# Battery_Monitoring.net
KiCad netlist of a schematic drawn in Altium Designer
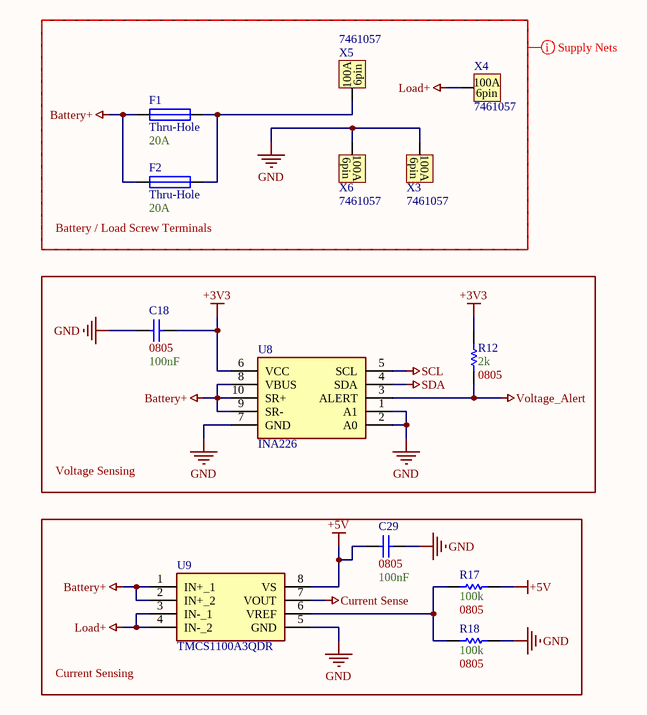
[diagram p0: Battery Monitoring.SchDoc]

(export (version "E")
  (design (tool "Eeschema 10.0.6"))
  (components
    (comp (ref "C18")
      (value "[Cap] SMD Nonpolarized")
      (footprint "[Cap] SMD 0805")
      (fields (field (name "SIZE PACKAGE") "0805") (field (name "CAPACITANCE") "100nF"))
      (libsource (lib "RADM Components") (part "[Cap] SMD Nonpolarized"))
    )
    (comp (ref "C29")
      (value "[Cap] SMD Nonpolarized")
      (footprint "[Cap] SMD 0805")
      (fields (field (name "SIZE PACKAGE") "0805") (field (name "CAPACITANCE") "100nF"))
      (libsource (lib "RADM Components") (part "[Cap] SMD Nonpolarized"))
    )
    (comp (ref "F1")
      (value "Thru-Hole")
      (footprint "[Fuse] Blade (2)")
      (fields (field (name "CAPACITY") "20A"))
      (libsource (lib "RADM Components") (part "[Fuse] Thru-Hole Blade"))
    )
    (comp (ref "F2")
      (value "Thru-Hole")
      (footprint "[Fuse] Blade (2)")
      (fields (field (name "CAPACITY") "20A"))
      (libsource (lib "RADM Components") (part "[Fuse] Thru-Hole Blade"))
    )
    (comp (ref "R12")
      (value "[Res] SMD Resistor")
      (footprint "[Res] SMD 0805")
      (fields (field (name "RESISTANCE") "2k") (field (name "SIZE PACKAGE") "0805"))
      (libsource (lib "RADM Components") (part "[Res] SMD Resistor"))
    )
    (comp (ref "R17")
      (value "[Res] SMD Resistor")
      (footprint "[Res] SMD 0805")
      (fields (field (name "RESISTANCE") "100k") (field (name "SIZE PACKAGE") "0805"))
      (libsource (lib "RADM Components") (part "[Res] SMD Resistor"))
    )
    (comp (ref "R18")
      (value "[Res] SMD Resistor")
      (footprint "[Res] SMD 0805")
      (fields (field (name "RESISTANCE") "100k") (field (name "SIZE PACKAGE") "0805"))
      (libsource (lib "RADM Components") (part "[Res] SMD Resistor"))
    )
    (comp (ref "U8")
      (value "INA226")
      (footprint "[IC] Battery Voltage Monitor (36V)")
      (description "INA226AIDGST")
      (libsource (lib "RADM Components") (part "[IC] Battery Voltage Monitor (36V)"))
    )
    (comp (ref "U9")
      (value "TMCS1100A3QDR")
      (footprint "[IC] Hall Effect Current Sensor")
      (description "TMCS1100")
      (libsource (lib "RADM Components") (part "[IC] Hall Effect Current Sensor"))
    )
    (comp (ref "X3")
      (value "7461057")
      (footprint "[Port] Shank Connector (100A)")
      (description "7461057, internal thread")
      (libsource (lib "") (part "[Port] Shank Connector (100A)_1"))
    )
    (comp (ref "X4")
      (value "7461057")
      (footprint "[Port] Shank Connector (100A)")
      (description "7461057, internal thread")
      (libsource (lib "") (part "[Port] Shank Connector (100A)_2"))
    )
    (comp (ref "X5")
      (value "7461057")
      (footprint "[Port] Shank Connector (100A)")
      (description "7461057, internal thread")
      (libsource (lib "RADM Components") (part "[Port] Shank Connector (100A)"))
    )
    (comp (ref "X6")
      (value "7461057")
      (footprint "[Port] Shank Connector (100A)")
      (description "7461057, internal thread")
      (libsource (lib "") (part "[Port] Shank Connector (100A)_1"))
    )
  )
  (nets
    (net (code "1") (name "+3V3") (class "Default")
      (node (ref "C18") (pin "1") (pinfunction "1_1") (pintype "passive"))
      (node (ref "R12") (pin "2") (pinfunction "2_2") (pintype "passive"))
      (node (ref "U8") (pin "6") (pinfunction "VCC_6") (pintype "passive"))
    )
    (net (code "2") (name "+5V") (class "Default")
      (node (ref "C29") (pin "2") (pinfunction "2_2") (pintype "passive"))
      (node (ref "R17") (pin "2") (pinfunction "2_2") (pintype "passive"))
      (node (ref "U9") (pin "8") (pinfunction "VS_8") (pintype "passive"))
    )
    (net (code "3") (name "Battery+") (class "Default")
      (node (ref "F1") (pin "1") (pinfunction "1_1") (pintype "passive"))
      (node (ref "F2") (pin "1") (pinfunction "1_1") (pintype "passive"))
      (node (ref "U8") (pin "10") (pinfunction "SR+_10") (pintype "passive"))
      (node (ref "U8") (pin "8") (pinfunction "VBUS_8") (pintype "passive"))
      (node (ref "U8") (pin "9") (pinfunction "SR-_9") (pintype "passive"))
      (node (ref "U9") (pin "1") (pinfunction "IN+_1_1") (pintype "passive"))
      (node (ref "U9") (pin "2") (pinfunction "IN+_2_2") (pintype "passive"))
    )
    (net (code "4") (name "Current Sense") (class "Default")
      (node (ref "U9") (pin "7") (pinfunction "VOUT_7") (pintype "passive"))
    )
    (net (code "5") (name "GND") (class "Default")
      (node (ref "C18") (pin "2") (pinfunction "2_2") (pintype "passive"))
      (node (ref "C29") (pin "1") (pinfunction "1_1") (pintype "passive"))
      (node (ref "R18") (pin "1") (pinfunction "1_1") (pintype "passive"))
      (node (ref "U8") (pin "1") (pinfunction "A1_1") (pintype "passive"))
      (node (ref "U8") (pin "2") (pinfunction "A0_2") (pintype "passive"))
      (node (ref "U8") (pin "7") (pinfunction "GND_7") (pintype "passive"))
      (node (ref "U9") (pin "5") (pinfunction "GND_5") (pintype "passive"))
      (node (ref "X3") (pin "1") (pinfunction "4_1") (pintype "power_in"))
      (node (ref "X6") (pin "1") (pinfunction "4_1") (pintype "power_in"))
    )
    (net (code "6") (name "Load+") (class "Default")
      (node (ref "U9") (pin "3") (pinfunction "IN-_1_3") (pintype "passive"))
      (node (ref "U9") (pin "4") (pinfunction "IN-_2_4") (pintype "passive"))
      (node (ref "X4") (pin "1") (pinfunction "4_1") (pintype "power_in"))
    )
    (net (code "7") (name "Net-(U9-VREF)") (class "Default")
      (node (ref "R17") (pin "1") (pinfunction "1_1") (pintype "passive"))
      (node (ref "R18") (pin "2") (pinfunction "2_2") (pintype "passive"))
      (node (ref "U9") (pin "6") (pinfunction "VREF_6") (pintype "passive"))
    )
    (net (code "8") (name "Net-(X5-4)") (class "Default")
      (node (ref "F1") (pin "2") (pinfunction "2_2") (pintype "passive"))
      (node (ref "F2") (pin "2") (pinfunction "2_2") (pintype "passive"))
      (node (ref "X5") (pin "1") (pinfunction "4_1") (pintype "power_in"))
    )
    (net (code "9") (name "SCL") (class "Default")
      (node (ref "U8") (pin "5") (pinfunction "SCL_5") (pintype "passive"))
    )
    (net (code "10") (name "SDA") (class "Default")
      (node (ref "U8") (pin "4") (pinfunction "SDA_4") (pintype "passive"))
    )
    (net (code "11") (name "Voltage_Alert") (class "Default")
      (node (ref "R12") (pin "1") (pinfunction "1_1") (pintype "passive"))
      (node (ref "U8") (pin "3") (pinfunction "ALERT_3") (pintype "passive"))
    )
  )
)
